# SHDN-S03-V00-ShutdownSegment.net
KiCad netlist of a schematic drawn in Altium Designer
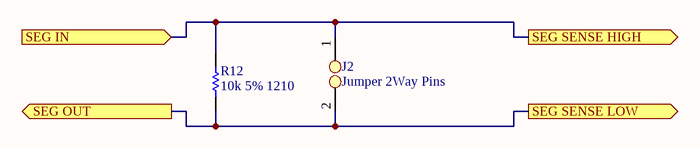
[diagram p0: SHDN-S03-V00-ShutdownSegment.SchDoc]

(export (version "E")
  (design (tool "Eeschema 10.0.6"))
  (components
    (comp (ref "J2")
      (value "Jumper 2Way Pins")
      (footprint "Jumper_2Way_Pin")
      (description "Jumper 2Way Vert Pins")
      (libsource (lib "QUTMS_JumperLibrary") (part "Jumper 2Way Vert Pins"))
    )
    (comp (ref "R12")
      (value "10k 5% 1210")
      (footprint "Res_ThinFilm_1210")
      (description "Resistor, SMD, 10k, 1W, 5%, 1210")
      (libsource (lib "StandardResistors") (part "10k 5% 1210"))
    )
  )
  (nets
    (net (code "1") (name "/SEG IN") (class "Default")
      (node (ref "J2") (pin "1") (pinfunction "1_1") (pintype "passive"))
      (node (ref "R12") (pin "2") (pinfunction "2_2") (pintype "passive"))
    )
    (net (code "2") (name "/SEG OUT") (class "Default")
      (node (ref "J2") (pin "2") (pinfunction "2_2") (pintype "passive"))
      (node (ref "R12") (pin "1") (pinfunction "1_1") (pintype "passive"))
    )
  )
)
